# brmecg.net
KiCad netlist of a schematic drawn in EAGLE
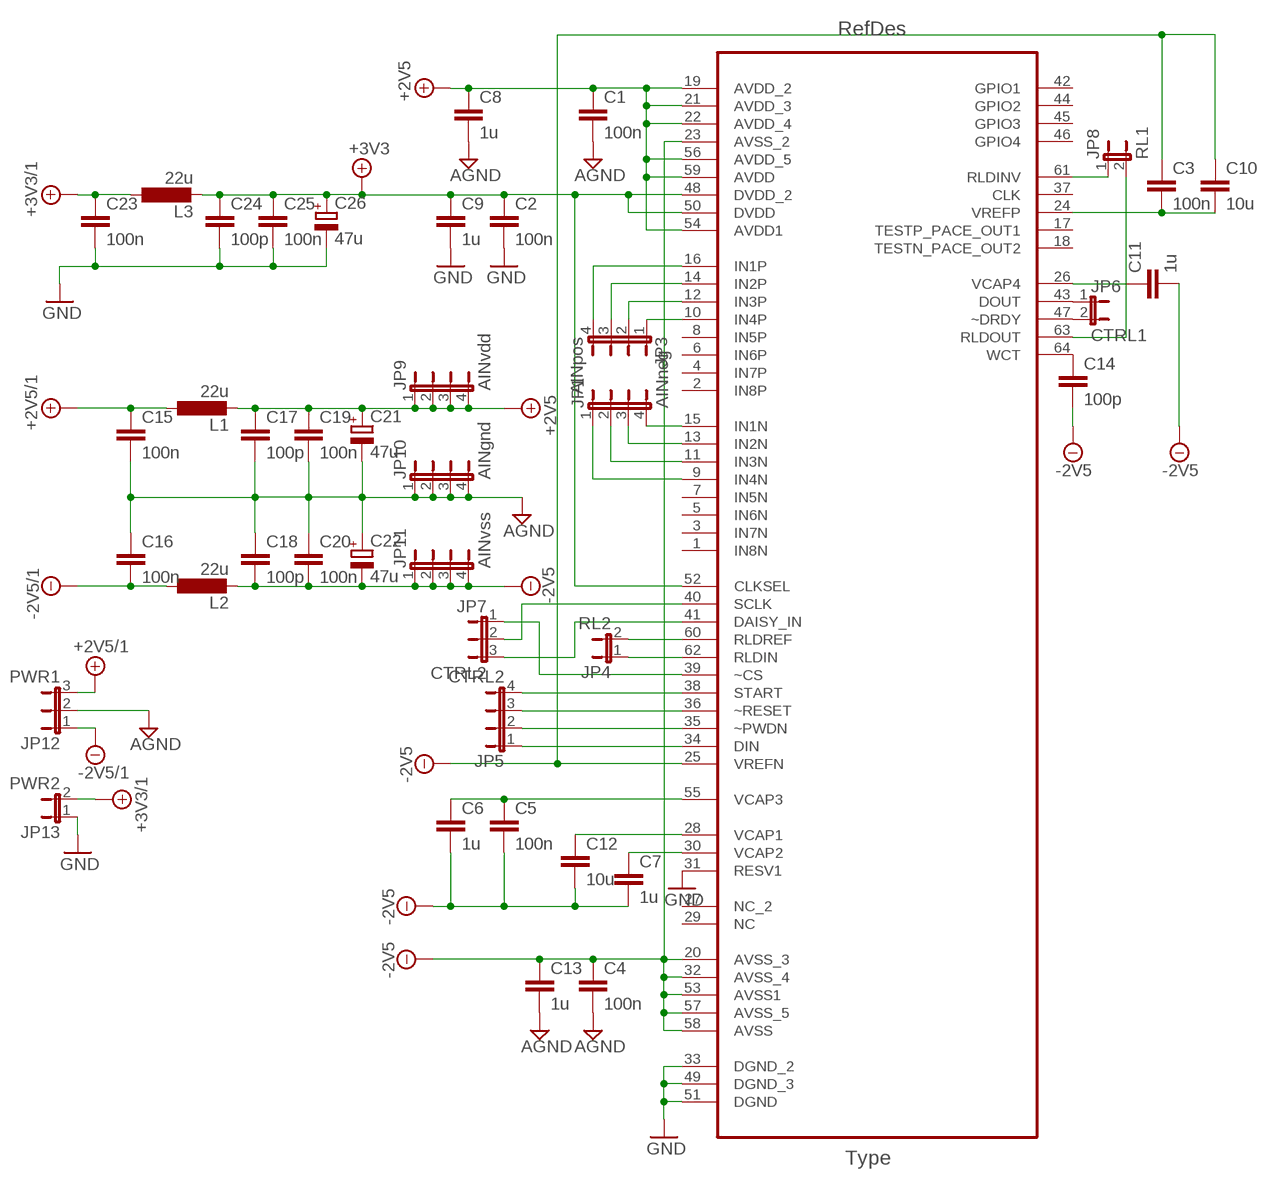
[diagram p0: schematic, sheet 1]

(export (version "E")
  (design (tool "Eeschema 10.0.6"))
  (components
    (comp (ref "C1")
      (value "100n")
      (footprint "eagle-import:C0603K")
      (libsource (lib "eagle-import") (part "C-EUC0603K"))
    )
    (comp (ref "C2")
      (value "100n")
      (footprint "eagle-import:C0603K")
      (libsource (lib "eagle-import") (part "C-EUC0603K"))
    )
    (comp (ref "C3")
      (value "100n")
      (footprint "eagle-import:C0603K")
      (libsource (lib "eagle-import") (part "C-EUC0603K"))
    )
    (comp (ref "C4")
      (value "100n")
      (footprint "eagle-import:C0603K")
      (libsource (lib "eagle-import") (part "C-EUC0603K"))
    )
    (comp (ref "C5")
      (value "100n")
      (footprint "eagle-import:C0603K")
      (libsource (lib "eagle-import") (part "C-EUC0603K"))
    )
    (comp (ref "C6")
      (value "1u")
      (footprint "eagle-import:C0805K")
      (libsource (lib "eagle-import") (part "C-EUC0805K"))
    )
    (comp (ref "C7")
      (value "1u")
      (footprint "eagle-import:C0805K")
      (libsource (lib "eagle-import") (part "C-EUC0805K"))
    )
    (comp (ref "C8")
      (value "1u")
      (footprint "eagle-import:C0805K")
      (libsource (lib "eagle-import") (part "C-EUC0805K"))
    )
    (comp (ref "C9")
      (value "1u")
      (footprint "eagle-import:C0805K")
      (libsource (lib "eagle-import") (part "C-EUC0805K"))
    )
    (comp (ref "C10")
      (value "10u")
      (footprint "eagle-import:C0805K")
      (libsource (lib "eagle-import") (part "C-EUC0805K"))
    )
    (comp (ref "C11")
      (value "1u")
      (footprint "eagle-import:C0805K")
      (libsource (lib "eagle-import") (part "C-EUC0805K"))
    )
    (comp (ref "C12")
      (value "10u")
      (footprint "eagle-import:C0805K")
      (libsource (lib "eagle-import") (part "C-EUC0805K"))
    )
    (comp (ref "C13")
      (value "1u")
      (footprint "eagle-import:C0805K")
      (libsource (lib "eagle-import") (part "C-EUC0805K"))
    )
    (comp (ref "C14")
      (value "100p")
      (footprint "eagle-import:C0603K")
      (libsource (lib "eagle-import") (part "C-EUC0603K"))
    )
    (comp (ref "C15")
      (value "100n")
      (footprint "eagle-import:C0603K")
      (libsource (lib "eagle-import") (part "C-EUC0603K"))
    )
    (comp (ref "C16")
      (value "100n")
      (footprint "eagle-import:C0603K")
      (libsource (lib "eagle-import") (part "C-EUC0603K"))
    )
    (comp (ref "C17")
      (value "100p")
      (footprint "eagle-import:C0603K")
      (libsource (lib "eagle-import") (part "C-EUC0603K"))
    )
    (comp (ref "C18")
      (value "100p")
      (footprint "eagle-import:C0603K")
      (libsource (lib "eagle-import") (part "C-EUC0603K"))
    )
    (comp (ref "C19")
      (value "100n")
      (footprint "eagle-import:C0603K")
      (libsource (lib "eagle-import") (part "C-EUC0603K"))
    )
    (comp (ref "C20")
      (value "100n")
      (footprint "eagle-import:C0603K")
      (libsource (lib "eagle-import") (part "C-EUC0603K"))
    )
    (comp (ref "C21")
      (value "47u")
      (footprint "eagle-import:SMC_C")
      (libsource (lib "eagle-import") (part "CPOL-EUSMCC"))
    )
    (comp (ref "C22")
      (value "47u")
      (footprint "eagle-import:SMC_C")
      (libsource (lib "eagle-import") (part "CPOL-EUSMCC"))
    )
    (comp (ref "C23")
      (value "100n")
      (footprint "eagle-import:C0603K")
      (libsource (lib "eagle-import") (part "C-EUC0603K"))
    )
    (comp (ref "C24")
      (value "100p")
      (footprint "eagle-import:C0603K")
      (libsource (lib "eagle-import") (part "C-EUC0603K"))
    )
    (comp (ref "C25")
      (value "100n")
      (footprint "eagle-import:C0603K")
      (libsource (lib "eagle-import") (part "C-EUC0603K"))
    )
    (comp (ref "C26")
      (value "47u")
      (footprint "eagle-import:SMC_C")
      (libsource (lib "eagle-import") (part "CPOL-EUSMCC"))
    )
    (comp (ref "JP1")
      (value "AINneg")
      (footprint "eagle-import:JP4")
      (libsource (lib "eagle-import") (part "JP4E"))
    )
    (comp (ref "JP3")
      (value "AINpos")
      (footprint "eagle-import:JP4")
      (libsource (lib "eagle-import") (part "JP4E"))
    )
    (comp (ref "JP4")
      (value "RL2")
      (footprint "eagle-import:JP1")
      (libsource (lib "eagle-import") (part "JP1E"))
    )
    (comp (ref "JP5")
      (value "CTRL2")
      (footprint "eagle-import:JP4")
      (libsource (lib "eagle-import") (part "JP4E"))
    )
    (comp (ref "JP6")
      (value "CTRL1")
      (footprint "eagle-import:JP1")
      (libsource (lib "eagle-import") (part "JP1E"))
    )
    (comp (ref "JP7")
      (value "CTRL2")
      (footprint "eagle-import:JP2")
      (libsource (lib "eagle-import") (part "JP2E"))
    )
    (comp (ref "JP8")
      (value "RL1")
      (footprint "eagle-import:JP1")
      (libsource (lib "eagle-import") (part "JP1E"))
    )
    (comp (ref "JP9")
      (value "AINvdd")
      (footprint "eagle-import:JP4")
      (libsource (lib "eagle-import") (part "JP4E"))
    )
    (comp (ref "JP10")
      (value "AINgnd")
      (footprint "eagle-import:JP4")
      (libsource (lib "eagle-import") (part "JP4E"))
    )
    (comp (ref "JP11")
      (value "AINvss")
      (footprint "eagle-import:JP4")
      (libsource (lib "eagle-import") (part "JP4E"))
    )
    (comp (ref "JP12")
      (value "PWR1")
      (footprint "eagle-import:JP2")
      (libsource (lib "eagle-import") (part "JP2E"))
    )
    (comp (ref "JP13")
      (value "PWR2")
      (footprint "eagle-import:JP1")
      (libsource (lib "eagle-import") (part "JP1E"))
    )
    (comp (ref "L1")
      (value "22u")
      (footprint "eagle-import:L1812")
      (libsource (lib "eagle-import") (part "L-EUL1812"))
    )
    (comp (ref "L2")
      (value "22u")
      (footprint "eagle-import:L1812")
      (libsource (lib "eagle-import") (part "L-EUL1812"))
    )
    (comp (ref "L3")
      (value "22u")
      (footprint "eagle-import:L1812")
      (libsource (lib "eagle-import") (part "L-EUL1812"))
    )
    (comp (ref "U1")
      (value "ADS1194CPAG")
      (footprint "eagle-import:QFP50P1200X1200X120-64N")
      (libsource (lib "eagle-import") (part "ADS1194CPAG"))
    )
  )
  (nets
    (net (code "1") (name "+2V5") (class "Default")
      (node (ref "C1") (pin "1") (pinfunction "1_1") (pintype "passive"))
      (node (ref "C17") (pin "1") (pinfunction "1_1") (pintype "passive"))
      (node (ref "C19") (pin "1") (pinfunction "1_1") (pintype "passive"))
      (node (ref "C21") (pin "+") (pinfunction "+_+") (pintype "passive"))
      (node (ref "C8") (pin "1") (pinfunction "1_1") (pintype "passive"))
      (node (ref "JP9") (pin "1") (pinfunction "1_1") (pintype "passive"))
      (node (ref "JP9") (pin "2") (pinfunction "2_2") (pintype "passive"))
      (node (ref "JP9") (pin "3") (pinfunction "3_3") (pintype "passive"))
      (node (ref "JP9") (pin "4") (pinfunction "4_4") (pintype "passive"))
      (node (ref "L1") (pin "2") (pinfunction "2_2") (pintype "passive"))
      (node (ref "U1") (pin "19") (pinfunction "AVDD_2_19") (pintype "power_in"))
      (node (ref "U1") (pin "21") (pinfunction "AVDD_3_21") (pintype "power_in"))
      (node (ref "U1") (pin "22") (pinfunction "AVDD_4_22") (pintype "power_in"))
      (node (ref "U1") (pin "54") (pinfunction "AVDD1_54") (pintype "power_in"))
      (node (ref "U1") (pin "56") (pinfunction "AVDD_5_56") (pintype "power_in"))
      (node (ref "U1") (pin "59") (pinfunction "AVDD_59") (pintype "power_in"))
    )
    (net (code "2") (name "+2V5{slash}1") (class "Default")
      (node (ref "C15") (pin "1") (pinfunction "1_1") (pintype "passive"))
      (node (ref "JP12") (pin "3") (pinfunction "3_3") (pintype "passive"))
      (node (ref "L1") (pin "1") (pinfunction "1_1") (pintype "passive"))
    )
    (net (code "3") (name "+3V3") (class "Default")
      (node (ref "C2") (pin "1") (pinfunction "1_1") (pintype "passive"))
      (node (ref "C24") (pin "1") (pinfunction "1_1") (pintype "passive"))
      (node (ref "C25") (pin "1") (pinfunction "1_1") (pintype "passive"))
      (node (ref "C26") (pin "+") (pinfunction "+_+") (pintype "passive"))
      (node (ref "C9") (pin "1") (pinfunction "1_1") (pintype "passive"))
      (node (ref "L3") (pin "2") (pinfunction "2_2") (pintype "passive"))
      (node (ref "U1") (pin "48") (pinfunction "DVDD_2_48") (pintype "power_in"))
      (node (ref "U1") (pin "50") (pinfunction "DVDD_50") (pintype "power_in"))
      (node (ref "U1") (pin "52") (pinfunction "CLKSEL_52") (pintype "input"))
    )
    (net (code "4") (name "+3V3{slash}1") (class "Default")
      (node (ref "C23") (pin "1") (pinfunction "1_1") (pintype "passive"))
      (node (ref "JP13") (pin "2") (pinfunction "2_2") (pintype "passive"))
      (node (ref "L3") (pin "1") (pinfunction "1_1") (pintype "passive"))
    )
    (net (code "5") (name "-2V5") (class "Default")
      (node (ref "C10") (pin "1") (pinfunction "1_1") (pintype "passive"))
      (node (ref "C11") (pin "2") (pinfunction "2_2") (pintype "passive"))
      (node (ref "C12") (pin "2") (pinfunction "2_2") (pintype "passive"))
      (node (ref "C13") (pin "1") (pinfunction "1_1") (pintype "passive"))
      (node (ref "C14") (pin "2") (pinfunction "2_2") (pintype "passive"))
      (node (ref "C18") (pin "2") (pinfunction "2_2") (pintype "passive"))
      (node (ref "C20") (pin "2") (pinfunction "2_2") (pintype "passive"))
      (node (ref "C22") (pin "-") (pinfunction "-_-") (pintype "passive"))
      (node (ref "C3") (pin "1") (pinfunction "1_1") (pintype "passive"))
      (node (ref "C4") (pin "1") (pinfunction "1_1") (pintype "passive"))
      (node (ref "C5") (pin "2") (pinfunction "2_2") (pintype "passive"))
      (node (ref "C6") (pin "2") (pinfunction "2_2") (pintype "passive"))
      (node (ref "C7") (pin "2") (pinfunction "2_2") (pintype "passive"))
      (node (ref "JP11") (pin "1") (pinfunction "1_1") (pintype "passive"))
      (node (ref "JP11") (pin "2") (pinfunction "2_2") (pintype "passive"))
      (node (ref "JP11") (pin "3") (pinfunction "3_3") (pintype "passive"))
      (node (ref "JP11") (pin "4") (pinfunction "4_4") (pintype "passive"))
      (node (ref "L2") (pin "2") (pinfunction "2_2") (pintype "passive"))
      (node (ref "U1") (pin "20") (pinfunction "AVSS_3_20") (pintype "power_in"))
      (node (ref "U1") (pin "23") (pinfunction "AVSS_2_23") (pintype "power_in"))
      (node (ref "U1") (pin "25") (pinfunction "VREFN_25") (pintype "input"))
      (node (ref "U1") (pin "32") (pinfunction "AVSS_4_32") (pintype "power_in"))
      (node (ref "U1") (pin "53") (pinfunction "AVSS1_53") (pintype "power_in"))
      (node (ref "U1") (pin "57") (pinfunction "AVSS_5_57") (pintype "power_in"))
      (node (ref "U1") (pin "58") (pinfunction "AVSS_58") (pintype "power_in"))
    )
    (net (code "6") (name "-2V5{slash}1") (class "Default")
      (node (ref "C16") (pin "2") (pinfunction "2_2") (pintype "passive"))
      (node (ref "JP12") (pin "1") (pinfunction "1_1") (pintype "passive"))
      (node (ref "L2") (pin "1") (pinfunction "1_1") (pintype "passive"))
    )
    (net (code "7") (name "AGND") (class "Default")
      (node (ref "C1") (pin "2") (pinfunction "2_2") (pintype "passive"))
      (node (ref "C13") (pin "2") (pinfunction "2_2") (pintype "passive"))
      (node (ref "C15") (pin "2") (pinfunction "2_2") (pintype "passive"))
      (node (ref "C16") (pin "1") (pinfunction "1_1") (pintype "passive"))
      (node (ref "C17") (pin "2") (pinfunction "2_2") (pintype "passive"))
      (node (ref "C18") (pin "1") (pinfunction "1_1") (pintype "passive"))
      (node (ref "C19") (pin "2") (pinfunction "2_2") (pintype "passive"))
      (node (ref "C20") (pin "1") (pinfunction "1_1") (pintype "passive"))
      (node (ref "C21") (pin "-") (pinfunction "-_-") (pintype "passive"))
      (node (ref "C22") (pin "+") (pinfunction "+_+") (pintype "passive"))
      (node (ref "C4") (pin "2") (pinfunction "2_2") (pintype "passive"))
      (node (ref "C8") (pin "2") (pinfunction "2_2") (pintype "passive"))
      (node (ref "JP10") (pin "1") (pinfunction "1_1") (pintype "passive"))
      (node (ref "JP10") (pin "2") (pinfunction "2_2") (pintype "passive"))
      (node (ref "JP10") (pin "3") (pinfunction "3_3") (pintype "passive"))
      (node (ref "JP10") (pin "4") (pinfunction "4_4") (pintype "passive"))
      (node (ref "JP12") (pin "2") (pinfunction "2_2") (pintype "passive"))
    )
    (net (code "8") (name "GND") (class "Default")
      (node (ref "C2") (pin "2") (pinfunction "2_2") (pintype "passive"))
      (node (ref "C23") (pin "2") (pinfunction "2_2") (pintype "passive"))
      (node (ref "C24") (pin "2") (pinfunction "2_2") (pintype "passive"))
      (node (ref "C25") (pin "2") (pinfunction "2_2") (pintype "passive"))
      (node (ref "C26") (pin "-") (pinfunction "-_-") (pintype "passive"))
      (node (ref "C9") (pin "2") (pinfunction "2_2") (pintype "passive"))
      (node (ref "JP13") (pin "1") (pinfunction "1_1") (pintype "passive"))
      (node (ref "U1") (pin "31") (pinfunction "RESV1_31") (pintype "passive"))
      (node (ref "U1") (pin "33") (pinfunction "DGND_2_33") (pintype "passive"))
      (node (ref "U1") (pin "49") (pinfunction "DGND_3_49") (pintype "passive"))
      (node (ref "U1") (pin "51") (pinfunction "DGND_51") (pintype "passive"))
    )
    (net (code "9") (name "Net-(U1-DAISY_IN)") (class "Default")
      (node (ref "JP7") (pin "3") (pinfunction "3_3") (pintype "passive"))
      (node (ref "U1") (pin "41") (pinfunction "DAISY_IN_41") (pintype "input"))
    )
    (net (code "10") (name "Net-(U1-DIN)") (class "Default")
      (node (ref "JP5") (pin "1") (pinfunction "1_1") (pintype "passive"))
      (node (ref "U1") (pin "34") (pinfunction "DIN_34") (pintype "input"))
    )
    (net (code "11") (name "Net-(U1-DOUT)") (class "Default")
      (node (ref "JP6") (pin "1") (pinfunction "1_1") (pintype "passive"))
      (node (ref "U1") (pin "43") (pinfunction "DOUT_43") (pintype "output"))
    )
    (net (code "12") (name "Net-(U1-IN1N)") (class "Default")
      (node (ref "JP1") (pin "4") (pinfunction "4_4") (pintype "passive"))
      (node (ref "U1") (pin "15") (pinfunction "IN1N_15") (pintype "input"))
    )
    (net (code "13") (name "Net-(U1-IN1P)") (class "Default")
      (node (ref "JP3") (pin "4") (pinfunction "4_4") (pintype "passive"))
      (node (ref "U1") (pin "16") (pinfunction "IN1P_16") (pintype "input"))
    )
    (net (code "14") (name "Net-(U1-IN2N)") (class "Default")
      (node (ref "JP1") (pin "3") (pinfunction "3_3") (pintype "passive"))
      (node (ref "U1") (pin "13") (pinfunction "IN2N_13") (pintype "input"))
    )
    (net (code "15") (name "Net-(U1-IN2P)") (class "Default")
      (node (ref "JP3") (pin "3") (pinfunction "3_3") (pintype "passive"))
      (node (ref "U1") (pin "14") (pinfunction "IN2P_14") (pintype "input"))
    )
    (net (code "16") (name "Net-(U1-IN3N)") (class "Default")
      (node (ref "JP1") (pin "2") (pinfunction "2_2") (pintype "passive"))
      (node (ref "U1") (pin "11") (pinfunction "IN3N_11") (pintype "input"))
    )
    (net (code "17") (name "Net-(U1-IN3P)") (class "Default")
      (node (ref "JP3") (pin "2") (pinfunction "2_2") (pintype "passive"))
      (node (ref "U1") (pin "12") (pinfunction "IN3P_12") (pintype "input"))
    )
    (net (code "18") (name "Net-(U1-IN4N)") (class "Default")
      (node (ref "JP1") (pin "1") (pinfunction "1_1") (pintype "passive"))
      (node (ref "U1") (pin "9") (pinfunction "IN4N_9") (pintype "input"))
    )
    (net (code "19") (name "Net-(U1-IN4P)") (class "Default")
      (node (ref "JP3") (pin "1") (pinfunction "1_1") (pintype "passive"))
      (node (ref "U1") (pin "10") (pinfunction "IN4P_10") (pintype "input"))
    )
    (net (code "20") (name "Net-(U1-RLDIN)") (class "Default")
      (node (ref "JP4") (pin "1") (pinfunction "1_1") (pintype "passive"))
      (node (ref "U1") (pin "62") (pinfunction "RLDIN_62") (pintype "input"))
    )
    (net (code "21") (name "Net-(U1-RLDINV)") (class "Default")
      (node (ref "JP8") (pin "1") (pinfunction "1_1") (pintype "passive"))
      (node (ref "U1") (pin "61") (pinfunction "RLDINV_61") (pintype "bidirectional"))
    )
    (net (code "22") (name "Net-(U1-RLDOUT)") (class "Default")
      (node (ref "JP8") (pin "2") (pinfunction "2_2") (pintype "passive"))
      (node (ref "U1") (pin "63") (pinfunction "RLDOUT_63") (pintype "output"))
    )
    (net (code "23") (name "Net-(U1-RLDREF)") (class "Default")
      (node (ref "JP4") (pin "2") (pinfunction "2_2") (pintype "passive"))
      (node (ref "U1") (pin "60") (pinfunction "RLDREF_60") (pintype "input"))
    )
    (net (code "24") (name "Net-(U1-SCLK)") (class "Default")
      (node (ref "JP7") (pin "2") (pinfunction "2_2") (pintype "passive"))
      (node (ref "U1") (pin "40") (pinfunction "SCLK_40") (pintype "input"))
    )
    (net (code "25") (name "Net-(U1-START)") (class "Default")
      (node (ref "JP5") (pin "4") (pinfunction "4_4") (pintype "passive"))
      (node (ref "U1") (pin "38") (pinfunction "START_38") (pintype "input"))
    )
    (net (code "26") (name "Net-(U1-VCAP1)") (class "Default")
      (node (ref "C12") (pin "1") (pinfunction "1_1") (pintype "passive"))
      (node (ref "U1") (pin "28") (pinfunction "VCAP1_28") (pintype "passive"))
    )
    (net (code "27") (name "Net-(U1-VCAP2)") (class "Default")
      (node (ref "C7") (pin "1") (pinfunction "1_1") (pintype "passive"))
      (node (ref "U1") (pin "30") (pinfunction "VCAP2_30") (pintype "passive"))
    )
    (net (code "28") (name "Net-(U1-VCAP3)") (class "Default")
      (node (ref "C5") (pin "1") (pinfunction "1_1") (pintype "passive"))
      (node (ref "C6") (pin "1") (pinfunction "1_1") (pintype "passive"))
      (node (ref "U1") (pin "55") (pinfunction "VCAP3_55") (pintype "passive"))
    )
    (net (code "29") (name "Net-(U1-VCAP4)") (class "Default")
      (node (ref "C11") (pin "1") (pinfunction "1_1") (pintype "passive"))
      (node (ref "U1") (pin "26") (pinfunction "VCAP4_26") (pintype "output"))
    )
    (net (code "30") (name "Net-(U1-VREFP)") (class "Default")
      (node (ref "C10") (pin "2") (pinfunction "2_2") (pintype "passive"))
      (node (ref "C3") (pin "2") (pinfunction "2_2") (pintype "passive"))
      (node (ref "U1") (pin "24") (pinfunction "VREFP_24") (pintype "bidirectional"))
    )
    (net (code "31") (name "Net-(U1-WCT)") (class "Default")
      (node (ref "C14") (pin "1") (pinfunction "1_1") (pintype "passive"))
      (node (ref "U1") (pin "64") (pinfunction "WCT_64") (pintype "output"))
    )
    (net (code "32") (name "Net-(U1-~{CS})") (class "Default")
      (node (ref "JP7") (pin "1") (pinfunction "1_1") (pintype "passive"))
      (node (ref "U1") (pin "39") (pinfunction "~{CS}_39") (pintype "input"))
    )
    (net (code "33") (name "Net-(U1-~{DRDY})") (class "Default")
      (node (ref "JP6") (pin "2") (pinfunction "2_2") (pintype "passive"))
      (node (ref "U1") (pin "47") (pinfunction "~{DRDY}_47") (pintype "output"))
    )
    (net (code "34") (name "Net-(U1-~{PWDN})") (class "Default")
      (node (ref "JP5") (pin "2") (pinfunction "2_2") (pintype "passive"))
      (node (ref "U1") (pin "35") (pinfunction "~{PWDN}_35") (pintype "input"))
    )
    (net (code "35") (name "Net-(U1-~{RESET})") (class "Default")
      (node (ref "JP5") (pin "3") (pinfunction "3_3") (pintype "passive"))
      (node (ref "U1") (pin "36") (pinfunction "~{RESET}_36") (pintype "input"))
    )
    (net (code "36") (name "unconnected-(U1-CLK-Pad37)") (class "Default")
      (node (ref "U1") (pin "37") (pinfunction "CLK_37") (pintype "bidirectional"))
    )
    (net (code "37") (name "unconnected-(U1-GPIO1-Pad42)") (class "Default")
      (node (ref "U1") (pin "42") (pinfunction "GPIO1_42") (pintype "bidirectional"))
    )
    (net (code "38") (name "unconnected-(U1-GPIO2-Pad44)") (class "Default")
      (node (ref "U1") (pin "44") (pinfunction "GPIO2_44") (pintype "bidirectional"))
    )
    (net (code "39") (name "unconnected-(U1-GPIO3-Pad45)") (class "Default")
      (node (ref "U1") (pin "45") (pinfunction "GPIO3_45") (pintype "bidirectional"))
    )
    (net (code "40") (name "unconnected-(U1-GPIO4-Pad46)") (class "Default")
      (node (ref "U1") (pin "46") (pinfunction "GPIO4_46") (pintype "bidirectional"))
    )
    (net (code "41") (name "unconnected-(U1-IN5N-Pad7)") (class "Default")
      (node (ref "U1") (pin "7") (pinfunction "IN5N_7") (pintype "input"))
    )
    (net (code "42") (name "unconnected-(U1-IN5P-Pad8)") (class "Default")
      (node (ref "U1") (pin "8") (pinfunction "IN5P_8") (pintype "input"))
    )
    (net (code "43") (name "unconnected-(U1-IN6N-Pad5)") (class "Default")
      (node (ref "U1") (pin "5") (pinfunction "IN6N_5") (pintype "input"))
    )
    (net (code "44") (name "unconnected-(U1-IN6P-Pad6)") (class "Default")
      (node (ref "U1") (pin "6") (pinfunction "IN6P_6") (pintype "input"))
    )
    (net (code "45") (name "unconnected-(U1-IN7N-Pad3)") (class "Default")
      (node (ref "U1") (pin "3") (pinfunction "IN7N_3") (pintype "input"))
    )
    (net (code "46") (name "unconnected-(U1-IN7P-Pad4)") (class "Default")
      (node (ref "U1") (pin "4") (pinfunction "IN7P_4") (pintype "input"))
    )
    (net (code "47") (name "unconnected-(U1-IN8N-Pad1)") (class "Default")
      (node (ref "U1") (pin "1") (pinfunction "IN8N_1") (pintype "input"))
    )
    (net (code "48") (name "unconnected-(U1-IN8P-Pad2)") (class "Default")
      (node (ref "U1") (pin "2") (pinfunction "IN8P_2") (pintype "input"))
    )
    (net (code "49") (name "unconnected-(U1-NC-Pad29)") (class "Default")
      (node (ref "U1") (pin "29") (pinfunction "NC_29") (pintype "no_connect"))
    )
    (net (code "50") (name "unconnected-(U1-NC_2-Pad27)") (class "Default")
      (node (ref "U1") (pin "27") (pinfunction "NC_2_27") (pintype "no_connect"))
    )
    (net (code "51") (name "unconnected-(U1-TESTN_PACE_OUT2-Pad18)") (class "Default")
      (node (ref "U1") (pin "18") (pinfunction "TESTN_PACE_OUT2_18") (pintype "bidirectional"))
    )
    (net (code "52") (name "unconnected-(U1-TESTP_PACE_OUT1-Pad17)") (class "Default")
      (node (ref "U1") (pin "17") (pinfunction "TESTP_PACE_OUT1_17") (pintype "bidirectional"))
    )
  )
)
